# DM2097_HUB.net
KiCad netlist of a schematic drawn in Altium Designer
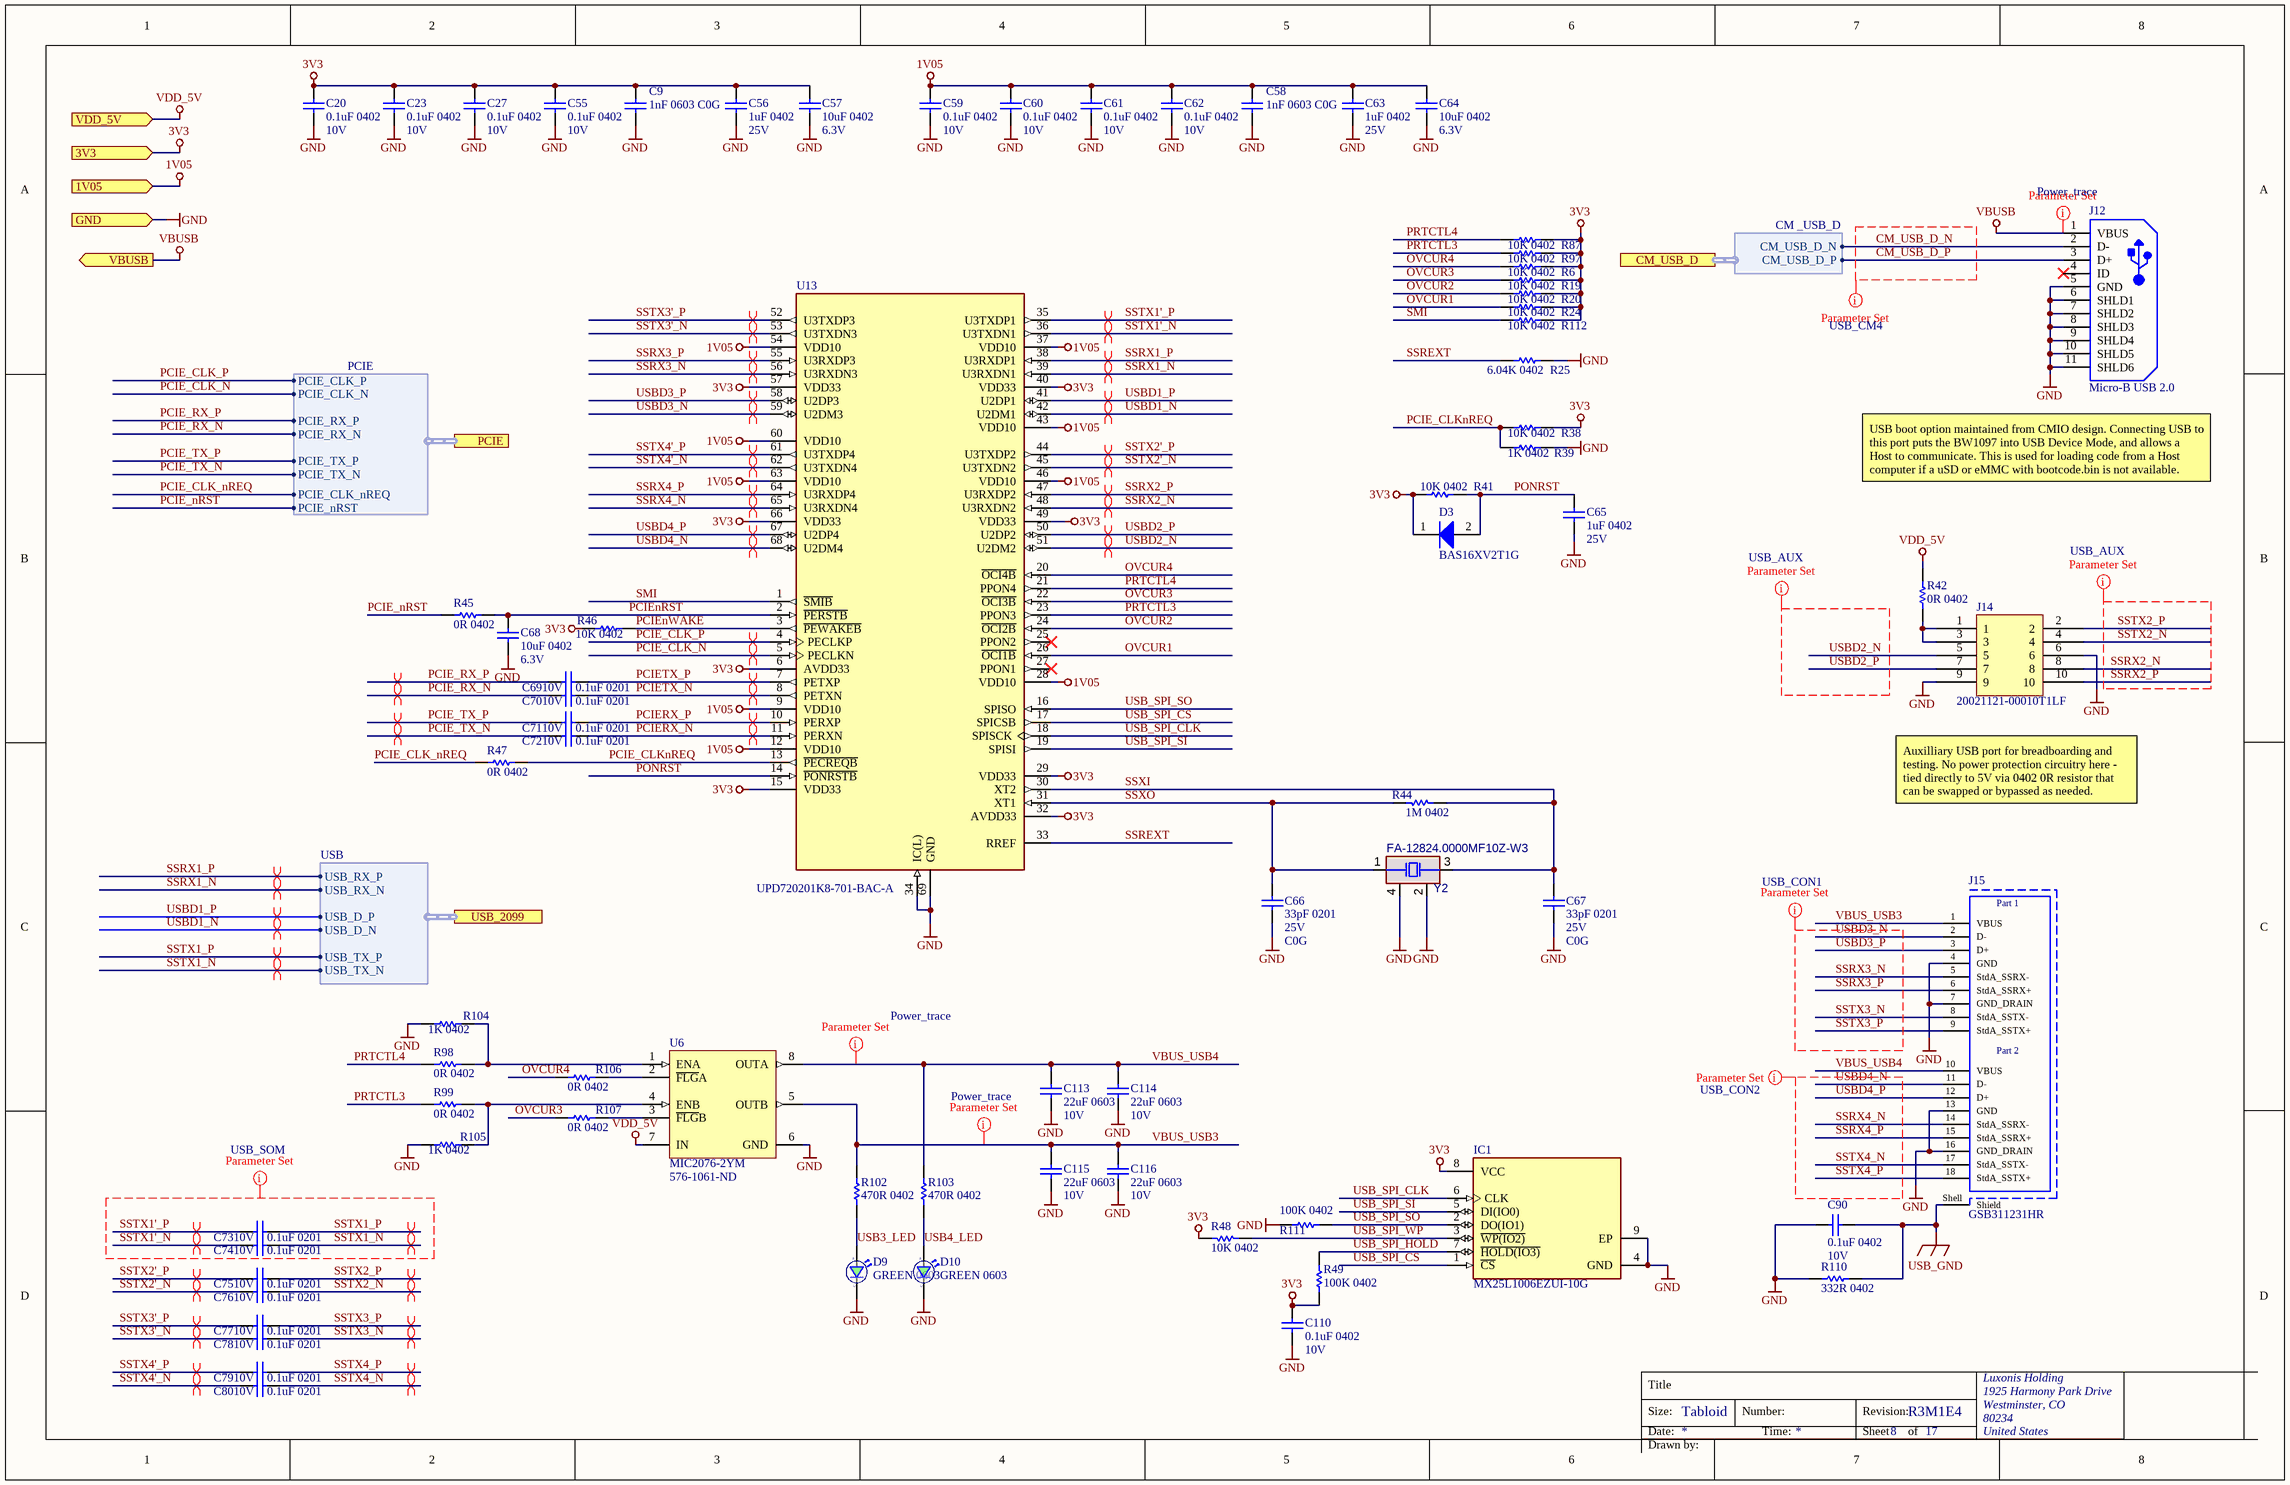
[diagram p0: DM2097_HUB.SchDoc]

(export (version "E")
  (design (tool "Eeschema 10.0.6"))
  (components
    (comp (ref "C9")
      (value "1nF 0603 C0G")
      (footprint "CAP_Altium_Vault_Generic:CAPC0603(1608)100_N")
      (description "CAP CER 1000PF 50V C0G/NP0 0603")
      (fields
        (field (name "MANUFACTURER") "Murata")
        (field (name "MANUFACTURER PART NUMBER") "GRM1885C1H102FA01D")
      )
      (libsource (lib "LuxonisMaster") (part "GRM1885C1H102FA01D"))
    )
    (comp (ref "C20")
      (value "0.1uF 0402")
      (footprint "CAP_Altium_Vault_Generic:CAPC0402(1005)70_N")
      (description "CAP CER 0.1UF 10V X7R 0402 5%")
      (fields (field (name "TOLERANCE") "5%") (field (name "VOLTAGE RATING") "10V"))
      (libsource (lib "LuxonisMaster") (part "GRM155R71A104JA01D"))
    )
    (comp (ref "C23")
      (value "0.1uF 0402")
      (footprint "CAP_Altium_Vault_Generic:CAPC0402(1005)70_N")
      (description "CAP CER 0.1UF 10V X7R 0402 5%")
      (fields (field (name "TOLERANCE") "5%") (field (name "VOLTAGE RATING") "10V"))
      (libsource (lib "LuxonisMaster") (part "GRM155R71A104JA01D"))
    )
    (comp (ref "C27")
      (value "0.1uF 0402")
      (footprint "CAP_Altium_Vault_Generic:CAPC0402(1005)70_N")
      (description "CAP CER 0.1UF 10V X7R 0402 5%")
      (fields (field (name "TOLERANCE") "5%") (field (name "VOLTAGE RATING") "10V"))
      (libsource (lib "LuxonisMaster") (part "GRM155R71A104JA01D"))
    )
    (comp (ref "C55")
      (value "0.1uF 0402")
      (footprint "CAP_Altium_Vault_Generic:CAPC0402(1005)70_N")
      (description "CAP CER 0.1UF 10V X7R 0402 5%")
      (fields (field (name "TOLERANCE") "5%") (field (name "VOLTAGE RATING") "10V"))
      (libsource (lib "LuxonisMaster") (part "GRM155R71A104JA01D"))
    )
    (comp (ref "C56")
      (value "1uF 0402")
      (footprint "CAP_Altium_Vault_Generic:CAPC0402(1005)70_N")
      (description "CAP CER 1UF 25V X5R 0402 10%")
      (fields
        (field (name "TOLERANCE") "10%")
        (field (name "VOLTAGE") "25V")
        (field (name "VOLTAGE RATING") "25V")
      )
      (libsource (lib "LuxonisMaster") (part "GRM155R61E105KA12D"))
    )
    (comp (ref "C57")
      (value "10uF 0402")
      (footprint "CAP_Altium_Vault_Generic:CAPC0402(1005)70_N")
      (description "CAP CER 10UF 6.3V X5R 0402 20%")
      (fields (field (name "TOLERANCE") "20%") (field (name "VOLTAGE RATING") "6.3V"))
      (libsource (lib "LuxonisMaster") (part "GRM155R60J106ME15D"))
    )
    (comp (ref "C58")
      (value "1nF 0603 C0G")
      (footprint "CAP_Altium_Vault_Generic:CAPC0603(1608)100_N")
      (description "CAP CER 1000PF 50V C0G/NP0 0603")
      (fields
        (field (name "MANUFACTURER") "Murata")
        (field (name "MANUFACTURER PART NUMBER") "GRM1885C1H102FA01D")
      )
      (libsource (lib "LuxonisMaster") (part "GRM1885C1H102FA01D"))
    )
    (comp (ref "C59")
      (value "0.1uF 0402")
      (footprint "CAP_Altium_Vault_Generic:CAPC0402(1005)70_N")
      (description "CAP CER 0.1UF 10V X7R 0402 5%")
      (fields (field (name "TOLERANCE") "5%") (field (name "VOLTAGE RATING") "10V"))
      (libsource (lib "LuxonisMaster") (part "GRM155R71A104JA01D"))
    )
    (comp (ref "C60")
      (value "0.1uF 0402")
      (footprint "CAP_Altium_Vault_Generic:CAPC0402(1005)70_N")
      (description "CAP CER 0.1UF 10V X7R 0402 5%")
      (fields (field (name "TOLERANCE") "5%") (field (name "VOLTAGE RATING") "10V"))
      (libsource (lib "LuxonisMaster") (part "GRM155R71A104JA01D"))
    )
    (comp (ref "C61")
      (value "0.1uF 0402")
      (footprint "CAP_Altium_Vault_Generic:CAPC0402(1005)70_N")
      (description "CAP CER 0.1UF 10V X7R 0402 5%")
      (fields (field (name "TOLERANCE") "5%") (field (name "VOLTAGE RATING") "10V"))
      (libsource (lib "LuxonisMaster") (part "GRM155R71A104JA01D"))
    )
    (comp (ref "C62")
      (value "0.1uF 0402")
      (footprint "CAP_Altium_Vault_Generic:CAPC0402(1005)70_N")
      (description "CAP CER 0.1UF 10V X7R 0402 5%")
      (fields (field (name "TOLERANCE") "5%") (field (name "VOLTAGE RATING") "10V"))
      (libsource (lib "LuxonisMaster") (part "GRM155R71A104JA01D"))
    )
    (comp (ref "C63")
      (value "1uF 0402")
      (footprint "CAP_Altium_Vault_Generic:CAPC0402(1005)70_N")
      (description "CAP CER 1UF 25V X5R 0402 10%")
      (fields
        (field (name "TOLERANCE") "10%")
        (field (name "VOLTAGE") "25V")
        (field (name "VOLTAGE RATING") "25V")
      )
      (libsource (lib "LuxonisMaster") (part "GRM155R61E105KA12D"))
    )
    (comp (ref "C64")
      (value "10uF 0402")
      (footprint "CAP_Altium_Vault_Generic:CAPC0402(1005)70_N")
      (description "CAP CER 10UF 6.3V X5R 0402 20%")
      (fields (field (name "TOLERANCE") "20%") (field (name "VOLTAGE RATING") "6.3V"))
      (libsource (lib "LuxonisMaster") (part "GRM155R60J106ME15D"))
    )
    (comp (ref "C65")
      (value "1uF 0402")
      (footprint "CAP_Altium_Vault_Generic:CAPC0402(1005)70_N")
      (description "CAP CER 1UF 25V X5R 0402 10%")
      (fields
        (field (name "TOLERANCE") "10%")
        (field (name "VOLTAGE") "25V")
        (field (name "VOLTAGE RATING") "25V")
      )
      (libsource (lib "LuxonisMaster") (part "GRM155R61E105KA12D"))
    )
    (comp (ref "C66")
      (value "33pF 0201")
      (footprint "CAP_Altium_Vault_Generic:CAPC0201(0603)33_L")
      (description "CAP CER 33PF 25V C0G/NP0 0201")
      (fields
        (field (name "TOLERANCE") "5%")
        (field (name "VOLTAGE RATING") "25V")
        (field (name "DIELECTRIC") "C0G")
      )
      (libsource (lib "LuxonisMaster") (part "GRM0335C1E330JA01D"))
    )
    (comp (ref "C67")
      (value "33pF 0201")
      (footprint "CAP_Altium_Vault_Generic:CAPC0201(0603)33_L")
      (description "CAP CER 33PF 25V C0G/NP0 0201")
      (fields
        (field (name "TOLERANCE") "5%")
        (field (name "VOLTAGE RATING") "25V")
        (field (name "DIELECTRIC") "C0G")
      )
      (libsource (lib "LuxonisMaster") (part "GRM0335C1E330JA01D"))
    )
    (comp (ref "C68")
      (value "10uF 0402")
      (footprint "CAP_Altium_Vault_Generic:CAPC0402(1005)70_N")
      (description "CAP CER 10UF 6.3V X5R 0402 20%")
      (fields (field (name "TOLERANCE") "20%") (field (name "VOLTAGE RATING") "6.3V"))
      (libsource (lib "LuxonisMaster") (part "GRM155R60J106ME15D"))
    )
    (comp (ref "C69")
      (value "0.1uF 0201")
      (footprint "CAP_Altium_Vault_Generic:CAPC0201(0603)33_L")
      (description "CAP CER 0.1UF 10V X5R 0201")
      (fields (field (name "TOLERANCE") "10%") (field (name "VOLTAGE") "10V"))
      (libsource (lib "LuxonisMaster") (part "GRM033R61A104KE15D"))
    )
    (comp (ref "C70")
      (value "0.1uF 0201")
      (footprint "CAP_Altium_Vault_Generic:CAPC0201(0603)33_L")
      (description "CAP CER 0.1UF 10V X5R 0201")
      (fields (field (name "TOLERANCE") "10%") (field (name "VOLTAGE") "10V"))
      (libsource (lib "LuxonisMaster") (part "GRM033R61A104KE15D"))
    )
    (comp (ref "C71")
      (value "0.1uF 0201")
      (footprint "CAP_Altium_Vault_Generic:CAPC0201(0603)33_L")
      (description "CAP CER 0.1UF 10V X5R 0201")
      (fields (field (name "TOLERANCE") "10%") (field (name "VOLTAGE") "10V"))
      (libsource (lib "LuxonisMaster") (part "GRM033R61A104KE15D"))
    )
    (comp (ref "C72")
      (value "0.1uF 0201")
      (footprint "CAP_Altium_Vault_Generic:CAPC0201(0603)33_L")
      (description "CAP CER 0.1UF 10V X5R 0201")
      (fields (field (name "TOLERANCE") "10%") (field (name "VOLTAGE") "10V"))
      (libsource (lib "LuxonisMaster") (part "GRM033R61A104KE15D"))
    )
    (comp (ref "C73")
      (value "0.1uF 0201")
      (footprint "CAP_Altium_Vault_Generic:CAPC0201(0603)33_L")
      (description "CAP CER 0.1UF 10V X5R 0201")
      (fields (field (name "TOLERANCE") "10%") (field (name "VOLTAGE") "10V"))
      (libsource (lib "LuxonisMaster") (part "GRM033R61A104KE15D"))
    )
    (comp (ref "C74")
      (value "0.1uF 0201")
      (footprint "CAP_Altium_Vault_Generic:CAPC0201(0603)33_L")
      (description "CAP CER 0.1UF 10V X5R 0201")
      (fields (field (name "TOLERANCE") "10%") (field (name "VOLTAGE") "10V"))
      (libsource (lib "LuxonisMaster") (part "GRM033R61A104KE15D"))
    )
    (comp (ref "C75")
      (value "0.1uF 0201")
      (footprint "CAP_Altium_Vault_Generic:CAPC0201(0603)33_L")
      (description "CAP CER 0.1UF 10V X5R 0201")
      (fields (field (name "TOLERANCE") "10%") (field (name "VOLTAGE") "10V"))
      (libsource (lib "LuxonisMaster") (part "GRM033R61A104KE15D"))
    )
    (comp (ref "C76")
      (value "0.1uF 0201")
      (footprint "CAP_Altium_Vault_Generic:CAPC0201(0603)33_L")
      (description "CAP CER 0.1UF 10V X5R 0201")
      (fields (field (name "TOLERANCE") "10%") (field (name "VOLTAGE") "10V"))
      (libsource (lib "LuxonisMaster") (part "GRM033R61A104KE15D"))
    )
    (comp (ref "C77")
      (value "0.1uF 0201")
      (footprint "CAP_Altium_Vault_Generic:CAPC0201(0603)33_L")
      (description "CAP CER 0.1UF 10V X5R 0201")
      (fields (field (name "TOLERANCE") "10%") (field (name "VOLTAGE") "10V"))
      (libsource (lib "LuxonisMaster") (part "GRM033R61A104KE15D"))
    )
    (comp (ref "C78")
      (value "0.1uF 0201")
      (footprint "CAP_Altium_Vault_Generic:CAPC0201(0603)33_L")
      (description "CAP CER 0.1UF 10V X5R 0201")
      (fields (field (name "TOLERANCE") "10%") (field (name "VOLTAGE") "10V"))
      (libsource (lib "LuxonisMaster") (part "GRM033R61A104KE15D"))
    )
    (comp (ref "C79")
      (value "0.1uF 0201")
      (footprint "CAP_Altium_Vault_Generic:CAPC0201(0603)33_L")
      (description "CAP CER 0.1UF 10V X5R 0201")
      (fields (field (name "TOLERANCE") "10%") (field (name "VOLTAGE") "10V"))
      (libsource (lib "LuxonisMaster") (part "GRM033R61A104KE15D"))
    )
    (comp (ref "C80")
      (value "0.1uF 0201")
      (footprint "CAP_Altium_Vault_Generic:CAPC0201(0603)33_L")
      (description "CAP CER 0.1UF 10V X5R 0201")
      (fields (field (name "TOLERANCE") "10%") (field (name "VOLTAGE") "10V"))
      (libsource (lib "LuxonisMaster") (part "GRM033R61A104KE15D"))
    )
    (comp (ref "C90")
      (value "0.1uF 0402")
      (footprint "CAP_Altium_Vault_Generic:CAPC0402(1005)70_N")
      (description "CAP CER 0.1UF 10V X7R 0402 5%")
      (fields (field (name "TOLERANCE") "5%") (field (name "VOLTAGE RATING") "10V"))
      (libsource (lib "LuxonisMaster") (part "GRM155R71A104JA01D"))
    )
    (comp (ref "C110")
      (value "0.1uF 0402")
      (footprint "CAP_Altium_Vault_Generic:CAPC0402(1005)70_N")
      (description "CAP CER 0.1UF 10V X7R 0402 5%")
      (fields (field (name "TOLERANCE") "5%") (field (name "VOLTAGE RATING") "10V"))
      (libsource (lib "LuxonisMaster") (part "GRM155R71A104JA01D"))
    )
    (comp (ref "C113")
      (value "22uF 0603")
      (footprint "CAP_Altium_Vault_Generic:CAPC0603(1608)100_N")
      (description "CAP CER 22UF 10V X5R 0603 20%")
      (fields (field (name "TOLERANCE") "20%") (field (name "VOLTAGE RATING") "10V"))
      (libsource (lib "LuxonisMaster") (part "GRM188R61A226ME15D"))
    )
    (comp (ref "C114")
      (value "22uF 0603")
      (footprint "CAP_Altium_Vault_Generic:CAPC0603(1608)100_N")
      (description "CAP CER 22UF 10V X5R 0603 20%")
      (fields (field (name "TOLERANCE") "20%") (field (name "VOLTAGE RATING") "10V"))
      (libsource (lib "LuxonisMaster") (part "GRM188R61A226ME15D"))
    )
    (comp (ref "C115")
      (value "22uF 0603")
      (footprint "CAP_Altium_Vault_Generic:CAPC0603(1608)100_N")
      (description "CAP CER 22UF 10V X5R 0603 20%")
      (fields (field (name "TOLERANCE") "20%") (field (name "VOLTAGE RATING") "10V"))
      (libsource (lib "LuxonisMaster") (part "GRM188R61A226ME15D"))
    )
    (comp (ref "C116")
      (value "22uF 0603")
      (footprint "CAP_Altium_Vault_Generic:CAPC0603(1608)100_N")
      (description "CAP CER 22UF 10V X5R 0603 20%")
      (fields (field (name "TOLERANCE") "20%") (field (name "VOLTAGE RATING") "10V"))
      (libsource (lib "LuxonisMaster") (part "GRM188R61A226ME15D"))
    )
    (comp (ref "D3")
      (value "BAS16XV2T1G")
      (footprint "BAS16XV2T1G")
      (description "DIODE GEN PURP 75V 200MA SOD523")
      (libsource (lib "Luxonis") (part "Symbol"))
    )
    (comp (ref "D9")
      (value "GREEN 0603")
      (footprint "LuxonisMaster:SML_D1xx8W")
      (description "LED GREEN DIFFUSED 0603 SMD Green 572nm LED Indication - Discrete 2.2V 0603 (1608 Metric)")
      (fields (field (name "MANUFACTURER") "Rohm") (field (name "MANUFACTURER PART NUMBER") "SML-D12M8WT86"))
      (libsource (lib "LuxonisMaster") (part "SML-D12M8WT86"))
    )
    (comp (ref "D10")
      (value "GREEN 0603")
      (footprint "LuxonisMaster:SML_D1xx8W")
      (description "LED GREEN DIFFUSED 0603 SMD Green 572nm LED Indication - Discrete 2.2V 0603 (1608 Metric)")
      (fields (field (name "MANUFACTURER") "Rohm") (field (name "MANUFACTURER PART NUMBER") "SML-D12M8WT86"))
      (libsource (lib "LuxonisMaster") (part "SML-D12M8WT86"))
    )
    (comp (ref "IC1")
      (value "MX25L1006EZUI-10G")
      (footprint "MX25L1006EZUI-10G-Footprint-1")
      (description "Flash, 512KX2, PDSO8")
      (libsource (lib "Luxonis LLC") (part "MX25L1006EZUI-10G-Symbol-1"))
    )
    (comp (ref "J12")
      (value "Micro-B USB 2.0")
      (footprint "LuxonisMaster:10118194-0001LF")
      (libsource (lib "LuxonisMaster") (part "10118194-0001LF"))
    )
    (comp (ref "J14")
      (value "20021121-00010T1LF")
      (footprint "LuxonisMaster:20021121-00010T1LF")
      (description "CONN HEADER SMD 10POS 1.27MM")
      (libsource (lib "LuxonisMaster") (part "20021121-00010T1LF"))
    )
    (comp (ref "J15")
      (value "GSB311231HR")
      (footprint "GSB311231HR")
      (description "USB Connector, 18 Contact(s), Female, Right Angle, Solder Terminal")
      (fields (field (name "MANUFACTURER") "Amphenol Commercial"))
      (libsource (lib "DM1097_R1M1E1") (part "GSB311231HR"))
    )
    (comp (ref "R6")
      (value "10K 0402")
      (footprint "RES_Altium_Vault_Generic:RESC0402(1005)_N")
      (fields (field (name "TOLERANCE") "1%"))
      (libsource (lib "LuxonisMaster") (part "RC0402FR-1310KL"))
    )
    (comp (ref "R19")
      (value "10K 0402")
      (footprint "RES_Altium_Vault_Generic:RESC0402(1005)_N")
      (fields (field (name "TOLERANCE") "1%"))
      (libsource (lib "LuxonisMaster") (part "RC0402FR-1310KL"))
    )
    (comp (ref "R20")
      (value "10K 0402")
      (footprint "RES_Altium_Vault_Generic:RESC0402(1005)_N")
      (fields (field (name "TOLERANCE") "1%"))
      (libsource (lib "LuxonisMaster") (part "RC0402FR-1310KL"))
    )
    (comp (ref "R24")
      (value "10K 0402")
      (footprint "RES_Altium_Vault_Generic:RESC0402(1005)_N")
      (fields (field (name "TOLERANCE") "1%"))
      (libsource (lib "LuxonisMaster") (part "RC0402FR-1310KL"))
    )
    (comp (ref "R25")
      (value "6.04K 0402")
      (footprint "RESC0402(1005)_L")
      (fields (field (name "TOLERANCE") "1%"))
      (libsource (lib "") (part "Symbol_1"))
    )
    (comp (ref "R38")
      (value "10K 0402")
      (footprint "RES_Altium_Vault_Generic:RESC0402(1005)_N")
      (fields (field (name "TOLERANCE") "1%"))
      (libsource (lib "LuxonisMaster") (part "RC0402FR-1310KL"))
    )
    (comp (ref "R39")
      (value "1K 0402")
      (footprint "RESC0402(1005)_L")
      (fields (field (name "TOLERANCE") "1%"))
      (libsource (lib "LuxonisMaster") (part "Symbol"))
    )
    (comp (ref "R41")
      (value "10K 0402")
      (footprint "RES_Altium_Vault_Generic:RESC0402(1005)_N")
      (fields (field (name "TOLERANCE") "1%"))
      (libsource (lib "LuxonisMaster") (part "RC0402FR-1310KL"))
    )
    (comp (ref "R42")
      (value "0R 0402")
      (footprint "RES_Altium_Vault_Generic:RESC0402(1005)_N")
      (description "RES SMD 0 OHM JUMPER 1/16W 0402")
      (fields (field (name "TOLERANCE") "5%"))
      (libsource (lib "LuxonisMaster") (part "CRCW04020000Z0ED"))
    )
    (comp (ref "R44")
      (value "1M 0402")
      (footprint "RES_Altium_Vault_Generic:RESC0402(1005)_N")
      (description "RES SMD 1M OHM 1% 1/16W 0402")
      (fields (field (name "TOLERANCE") "1%"))
      (libsource (lib "LuxonisMaster") (part "RC0402FR-071ML"))
    )
    (comp (ref "R45")
      (value "0R 0402")
      (footprint "RES_Altium_Vault_Generic:RESC0402(1005)_N")
      (description "RES SMD 0 OHM JUMPER 1/16W 0402")
      (fields (field (name "TOLERANCE") "5%"))
      (libsource (lib "LuxonisMaster") (part "CRCW04020000Z0ED"))
    )
    (comp (ref "R46")
      (value "10K 0402")
      (footprint "RES_Altium_Vault_Generic:RESC0402(1005)_N")
      (fields (field (name "TOLERANCE") "1%"))
      (libsource (lib "LuxonisMaster") (part "RC0402FR-1310KL"))
    )
    (comp (ref "R47")
      (value "0R 0402")
      (footprint "RES_Altium_Vault_Generic:RESC0402(1005)_N")
      (description "RES SMD 0 OHM JUMPER 1/16W 0402")
      (fields (field (name "TOLERANCE") "5%"))
      (libsource (lib "LuxonisMaster") (part "CRCW04020000Z0ED"))
    )
    (comp (ref "R48")
      (value "10K 0402")
      (footprint "RES_Altium_Vault_Generic:RESC0402(1005)_N")
      (fields (field (name "TOLERANCE") "1%"))
      (libsource (lib "LuxonisMaster") (part "RC0402FR-1310KL"))
    )
    (comp (ref "R49")
      (value "100K 0402")
      (footprint "RES_Altium_Vault_Generic:RESC0402(1005)_L")
      (description "RES SMD 100K OHM 1% 1/16W 0402")
      (fields (field (name "TOLERANCE") "1%"))
      (libsource (lib "LuxonisMaster") (part "RC0402FR-07100KL"))
    )
    (comp (ref "R87")
      (value "10K 0402")
      (footprint "RES_Altium_Vault_Generic:RESC0402(1005)_N")
      (fields (field (name "TOLERANCE") "1%"))
      (libsource (lib "LuxonisMaster") (part "RC0402FR-1310KL"))
    )
    (comp (ref "R97")
      (value "10K 0402")
      (footprint "RES_Altium_Vault_Generic:RESC0402(1005)_N")
      (fields (field (name "TOLERANCE") "1%"))
      (libsource (lib "LuxonisMaster") (part "RC0402FR-1310KL"))
    )
    (comp (ref "R98")
      (value "0R 0402")
      (footprint "RES_Altium_Vault_Generic:RESC0402(1005)_N")
      (description "RES SMD 0 OHM JUMPER 1/16W 0402")
      (fields (field (name "TOLERANCE") "5%"))
      (libsource (lib "LuxonisMaster") (part "CRCW04020000Z0ED"))
    )
    (comp (ref "R99")
      (value "0R 0402")
      (footprint "RES_Altium_Vault_Generic:RESC0402(1005)_N")
      (description "RES SMD 0 OHM JUMPER 1/16W 0402")
      (fields (field (name "TOLERANCE") "5%"))
      (libsource (lib "LuxonisMaster") (part "CRCW04020000Z0ED"))
    )
    (comp (ref "R102")
      (value "470R 0402")
      (footprint "RES_Altium_Vault_Generic:RESC0402(1005)_N")
      (description "RES SMD 470 OHM 1% 1/16W 0402")
      (fields (field (name "TOLERANCE") "1%"))
      (libsource (lib "LuxonisMaster") (part "CRCW0402470RFKED"))
    )
    (comp (ref "R103")
      (value "470R 0402")
      (footprint "RES_Altium_Vault_Generic:RESC0402(1005)_N")
      (description "RES SMD 470 OHM 1% 1/16W 0402")
      (fields (field (name "TOLERANCE") "1%"))
      (libsource (lib "LuxonisMaster") (part "CRCW0402470RFKED"))
    )
    (comp (ref "R104")
      (value "1K 0402")
      (footprint "RESC0402(1005)_L")
      (fields (field (name "TOLERANCE") "1%"))
      (libsource (lib "LuxonisMaster") (part "Symbol"))
    )
    (comp (ref "R105")
      (value "1K 0402")
      (footprint "RESC0402(1005)_L")
      (fields (field (name "TOLERANCE") "1%"))
      (libsource (lib "LuxonisMaster") (part "Symbol"))
    )
    (comp (ref "R106")
      (value "0R 0402")
      (footprint "RES_Altium_Vault_Generic:RESC0402(1005)_N")
      (description "RES SMD 0 OHM JUMPER 1/16W 0402")
      (fields (field (name "TOLERANCE") "5%"))
      (libsource (lib "LuxonisMaster") (part "CRCW04020000Z0ED"))
    )
    (comp (ref "R107")
      (value "0R 0402")
      (footprint "RES_Altium_Vault_Generic:RESC0402(1005)_N")
      (description "RES SMD 0 OHM JUMPER 1/16W 0402")
      (fields (field (name "TOLERANCE") "5%"))
      (libsource (lib "LuxonisMaster") (part "CRCW04020000Z0ED"))
    )
    (comp (ref "R110")
      (value "332R 0402")
      (footprint "RES_Altium_Vault_Generic:RESC0402(1005)_N")
      (description "RES SMD 332 OHM 1% 1/16W 0402")
      (fields (field (name "TOLERANCE") "1%"))
      (libsource (lib "LuxonisMaster") (part "RC0402FR-07332RL"))
    )
    (comp (ref "R111")
      (value "100K 0402")
      (footprint "RES_Altium_Vault_Generic:RESC0402(1005)_L")
      (description "RES SMD 100K OHM 1% 1/16W 0402")
      (fields (field (name "TOLERANCE") "1%"))
      (libsource (lib "LuxonisMaster") (part "RC0402FR-07100KL"))
    )
    (comp (ref "R112")
      (value "10K 0402")
      (footprint "RES_Altium_Vault_Generic:RESC0402(1005)_N")
      (fields (field (name "TOLERANCE") "1%"))
      (libsource (lib "LuxonisMaster") (part "RC0402FR-1310KL"))
    )
    (comp (ref "U6")
      (value "MIC2076-2YM")
      (footprint "MIC2076-2YM")
      (description "Power Supply Support Circuit, Fixed, 2 Channel, 2.4, PDSO8")
      (fields (field (name "SUPPLIER PART NUMBER 1") "576-1061-ND"))
      (libsource (lib "DM1097_R1M1E1") (part "MIC2076-2YM"))
    )
    (comp (ref "U13")
      (value "UPD720201K8-701-BAC-A")
      (footprint "QFN40P800X800X90-69N")
      (description "USB Host Controller USB 3.0 USB Interface 68-QFN (8x8)")
      (fields (field (name "DIGI-KEY_PART_NUMBER") "UPD720201K8-701-BAC-A-ND"))
      (libsource (lib "Luxonis LLC") (part "UPD720201K8-701-BAC-A"))
    )
    (comp (ref "Y2")
      (value "FA-12824.0000MF10Z-W3")
      (footprint "EPSON-FA-128_V")
      (description "Crystal, 24 MHz, +/- 10 ppm, -20 to 75 degC, 4-Pin SMD, RoHS, Tape and Reel")
      (libsource (lib "Luxonis LLC") (part "CMP-00014-7"))
    )
  )
  (nets
    (net (code "5") (name "/CM_USB_D_N") (class "Default")
      (node (ref "J12") (pin "2") (pinfunction "D-_2") (pintype "passive"))
    )
    (net (code "6") (name "/CM_USB_D_P") (class "Default")
      (node (ref "J12") (pin "3") (pinfunction "D+_3") (pintype "passive"))
    )
    (net (code "7") (name "/OVCUR1") (class "Default")
      (node (ref "R24") (pin "1") (pinfunction "1_1") (pintype "passive"))
      (node (ref "U13") (pin "26") (pinfunction "~{OCI1B}_26") (pintype "input"))
    )
    (net (code "8") (name "/OVCUR2") (class "Default")
      (node (ref "R20") (pin "1") (pinfunction "1_1") (pintype "passive"))
      (node (ref "U13") (pin "24") (pinfunction "~{OCI2B}_24") (pintype "input"))
    )
    (net (code "9") (name "/OVCUR3") (class "Default")
      (node (ref "R107") (pin "2") (pinfunction "2_2") (pintype "passive"))
      (node (ref "R19") (pin "1") (pinfunction "1_1") (pintype "passive"))
      (node (ref "U13") (pin "22") (pinfunction "~{OCI3B}_22") (pintype "input"))
    )
    (net (code "10") (name "/OVCUR4") (class "Default")
      (node (ref "R106") (pin "2") (pinfunction "2_2") (pintype "passive"))
      (node (ref "R6") (pin "1") (pinfunction "1_1") (pintype "passive"))
      (node (ref "U13") (pin "20") (pinfunction "~{OCI4B}_20") (pintype "input"))
    )
    (net (code "11") (name "/PCIERX_N") (class "Default")
      (node (ref "C72") (pin "2") (pinfunction "2_2") (pintype "passive"))
      (node (ref "U13") (pin "11") (pinfunction "PERXN_11") (pintype "input"))
    )
    (net (code "12") (name "/PCIERX_P") (class "Default")
      (node (ref "C71") (pin "2") (pinfunction "2_2") (pintype "passive"))
      (node (ref "U13") (pin "10") (pinfunction "PERXP_10") (pintype "input"))
    )
    (net (code "13") (name "/PCIETX_N") (class "Default")
      (node (ref "C70") (pin "2") (pinfunction "2_2") (pintype "passive"))
      (node (ref "U13") (pin "8") (pinfunction "PETXN_8") (pintype "output"))
    )
    (net (code "14") (name "/PCIETX_P") (class "Default")
      (node (ref "C69") (pin "2") (pinfunction "2_2") (pintype "passive"))
      (node (ref "U13") (pin "7") (pinfunction "PETXP_7") (pintype "output"))
    )
    (net (code "15") (name "/PCIE_CLK_N") (class "Default")
      (node (ref "U13") (pin "5") (pinfunction "PECLKN_5") (pintype "input"))
    )
    (net (code "16") (name "/PCIE_CLK_P") (class "Default")
      (node (ref "U13") (pin "4") (pinfunction "PECLKP_4") (pintype "input"))
    )
    (net (code "17") (name "/PCIE_CLK_nREQ") (class "Default")
      (node (ref "R47") (pin "1") (pinfunction "1_1") (pintype "passive"))
    )
    (net (code "18") (name "/PCIE_CLKnREQ") (class "Default")
      (node (ref "R38") (pin "1") (pinfunction "1_1") (pintype "passive"))
      (node (ref "R39") (pin "1") (pinfunction "1_1") (pintype "passive"))
      (node (ref "R47") (pin "2") (pinfunction "2_2") (pintype "passive"))
      (node (ref "U13") (pin "13") (pinfunction "~{PECREQB}_13") (pintype "output"))
    )
    (net (code "19") (name "/PCIE_RX_N") (class "Default")
      (node (ref "C70") (pin "1") (pinfunction "1_1") (pintype "passive"))
    )
    (net (code "20") (name "/PCIE_RX_P") (class "Default")
      (node (ref "C69") (pin "1") (pinfunction "1_1") (pintype "passive"))
    )
    (net (code "21") (name "/PCIE_TX_N") (class "Default")
      (node (ref "C72") (pin "1") (pinfunction "1_1") (pintype "passive"))
    )
    (net (code "22") (name "/PCIE_TX_P") (class "Default")
      (node (ref "C71") (pin "1") (pinfunction "1_1") (pintype "passive"))
    )
    (net (code "23") (name "/PCIE_nRST") (class "Default")
      (node (ref "R45") (pin "1") (pinfunction "1_1") (pintype "passive"))
    )
    (net (code "24") (name "/PCIEnRST") (class "Default")
      (node (ref "C68") (pin "2") (pinfunction "2_2") (pintype "passive"))
      (node (ref "R45") (pin "2") (pinfunction "2_2") (pintype "passive"))
      (node (ref "U13") (pin "2") (pinfunction "~{PERSTB}_2") (pintype "input"))
    )
    (net (code "25") (name "/PCIEnWAKE") (class "Default")
      (node (ref "R46") (pin "2") (pinfunction "2_2") (pintype "passive"))
      (node (ref "U13") (pin "3") (pinfunction "~{PEWAKEB}_3") (pintype "output"))
    )
    (net (code "26") (name "/PONRST") (class "Default")
      (node (ref "C65") (pin "2") (pinfunction "2_2") (pintype "passive"))
      (node (ref "D3") (pin "2") (pinfunction "A_2") (pintype "passive"))
      (node (ref "R41") (pin "2") (pinfunction "2_2") (pintype "passive"))
      (node (ref "U13") (pin "14") (pinfunction "~{PONRSTB}_14") (pintype "input"))
    )
    (net (code "27") (name "/PRTCTL3") (class "Default")
      (node (ref "R97") (pin "1") (pinfunction "1_1") (pintype "passive"))
      (node (ref "R99") (pin "2") (pinfunction "2_2") (pintype "passive"))
      (node (ref "U13") (pin "23") (pinfunction "PPON3_23") (pintype "output"))
    )
    (net (code "28") (name "/PRTCTL4") (class "Default")
      (node (ref "R87") (pin "1") (pinfunction "1_1") (pintype "passive"))
      (node (ref "R98") (pin "2") (pinfunction "2_2") (pintype "passive"))
      (node (ref "U13") (pin "21") (pinfunction "PPON4_21") (pintype "output"))
    )
    (net (code "29") (name "/SMI") (class "Default")
      (node (ref "R112") (pin "1") (pinfunction "1_1") (pintype "passive"))
      (node (ref "U13") (pin "1") (pinfunction "~{SMIB}_1") (pintype "output"))
    )
    (net (code "30") (name "/SSREXT") (class "Default")
      (node (ref "R25") (pin "1") (pinfunction "1_1") (pintype "passive"))
      (node (ref "U13") (pin "33") (pinfunction "RREF_33") (pintype "passive"))
    )
    (net (code "31") (name "/SSRX1_N") (class "Default")
      (node (ref "U13") (pin "39") (pinfunction "U3RXDN1_39") (pintype "input"))
    )
    (net (code "32") (name "/SSRX1_P") (class "Default")
      (node (ref "U13") (pin "38") (pinfunction "U3RXDP1_38") (pintype "input"))
    )
    (net (code "33") (name "/SSRX2_N") (class "Default")
      (node (ref "J14") (pin "8") (pinfunction "8_8") (pintype "passive"))
      (node (ref "U13") (pin "48") (pinfunction "U3RXDN2_48") (pintype "input"))
    )
    (net (code "34") (name "/SSRX2_P") (class "Default")
      (node (ref "J14") (pin "10") (pinfunction "10_10") (pintype "passive"))
      (node (ref "U13") (pin "47") (pinfunction "U3RXDP2_47") (pintype "input"))
    )
    (net (code "35") (name "/SSRX3_N") (class "Default")
      (node (ref "J15") (pin "5") (pinfunction "StdA_SSRX-_5") (pintype "passive"))
      (node (ref "U13") (pin "56") (pinfunction "U3RXDN3_56") (pintype "input"))
    )
    (net (code "36") (name "/SSRX3_P") (class "Default")
      (node (ref "J15") (pin "6") (pinfunction "StdA_SSRX+_6") (pintype "passive"))
      (node (ref "U13") (pin "55") (pinfunction "U3RXDP3_55") (pintype "input"))
    )
    (net (code "37") (name "/SSRX4_N") (class "Default")
      (node (ref "J15") (pin "14") (pinfunction "StdA_SSRX-_14") (pintype "passive"))
      (node (ref "U13") (pin "65") (pinfunction "U3RXDN4_65") (pintype "input"))
    )
    (net (code "38") (name "/SSRX4_P") (class "Default")
      (node (ref "J15") (pin "15") (pinfunction "StdA_SSRX+_15") (pintype "passive"))
      (node (ref "U13") (pin "64") (pinfunction "U3RXDP4_64") (pintype "input"))
    )
    (net (code "39") (name "/SSTX1'_N") (class "Default")
      (node (ref "C74") (pin "1") (pinfunction "1_1") (pintype "passive"))
      (node (ref "U13") (pin "36") (pinfunction "U3TXDN1_36") (pintype "output"))
    )
    (net (code "40") (name "/SSTX1'_P") (class "Default")
      (node (ref "C73") (pin "1") (pinfunction "1_1") (pintype "passive"))
      (node (ref "U13") (pin "35") (pinfunction "U3TXDP1_35") (pintype "output"))
    )
    (net (code "41") (name "/SSTX1_N") (class "Default")
      (node (ref "C74") (pin "2") (pinfunction "2_2") (pintype "passive"))
    )
    (net (code "42") (name "/SSTX1_P") (class "Default")
      (node (ref "C73") (pin "2") (pinfunction "2_2") (pintype "passive"))
    )
    (net (code "43") (name "/SSTX2'_N") (class "Default")
      (node (ref "C76") (pin "1") (pinfunction "1_1") (pintype "passive"))
      (node (ref "U13") (pin "45") (pinfunction "U3TXDN2_45") (pintype "output"))
    )
    (net (code "44") (name "/SSTX2'_P") (class "Default")
      (node (ref "C75") (pin "1") (pinfunction "1_1") (pintype "passive"))
      (node (ref "U13") (pin "44") (pinfunction "U3TXDP2_44") (pintype "output"))
    )
    (net (code "45") (name "/SSTX2_N") (class "Default")
      (node (ref "C76") (pin "2") (pinfunction "2_2") (pintype "passive"))
      (node (ref "J14") (pin "4") (pinfunction "4_4") (pintype "passive"))
    )
    (net (code "46") (name "/SSTX2_P") (class "Default")
      (node (ref "C75") (pin "2") (pinfunction "2_2") (pintype "passive"))
      (node (ref "J14") (pin "2") (pinfunction "2_2") (pintype "passive"))
    )
    (net (code "47") (name "/SSTX3'_N") (class "Default")
      (node (ref "C78") (pin "1") (pinfunction "1_1") (pintype "passive"))
      (node (ref "U13") (pin "53") (pinfunction "U3TXDN3_53") (pintype "output"))
    )
    (net (code "48") (name "/SSTX3'_P") (class "Default")
      (node (ref "C77") (pin "1") (pinfunction "1_1") (pintype "passive"))
      (node (ref "U13") (pin "52") (pinfunction "U3TXDP3_52") (pintype "output"))
    )
    (net (code "49") (name "/SSTX3_N") (class "Default")
      (node (ref "C78") (pin "2") (pinfunction "2_2") (pintype "passive"))
      (node (ref "J15") (pin "8") (pinfunction "StdA_SSTX-_8") (pintype "passive"))
    )
    (net (code "50") (name "/SSTX3_P") (class "Default")
      (node (ref "C77") (pin "2") (pinfunction "2_2") (pintype "passive"))
      (node (ref "J15") (pin "9") (pinfunction "StdA_SSTX+_9") (pintype "passive"))
    )
    (net (code "51") (name "/SSTX4'_N") (class "Default")
      (node (ref "C80") (pin "1") (pinfunction "1_1") (pintype "passive"))
      (node (ref "U13") (pin "62") (pinfunction "U3TXDN4_62") (pintype "output"))
    )
    (net (code "52") (name "/SSTX4'_P") (class "Default")
      (node (ref "C79") (pin "1") (pinfunction "1_1") (pintype "passive"))
      (node (ref "U13") (pin "61") (pinfunction "U3TXDP4_61") (pintype "output"))
    )
    (net (code "53") (name "/SSTX4_N") (class "Default")
      (node (ref "C80") (pin "2") (pinfunction "2_2") (pintype "passive"))
      (node (ref "J15") (pin "17") (pinfunction "StdA_SSTX-_17") (pintype "passive"))
    )
    (net (code "54") (name "/SSTX4_P") (class "Default")
      (node (ref "C79") (pin "2") (pinfunction "2_2") (pintype "passive"))
      (node (ref "J15") (pin "18") (pinfunction "StdA_SSTX+_18") (pintype "passive"))
    )
    (net (code "55") (name "/SSXI") (class "Default")
      (node (ref "C67") (pin "2") (pinfunction "2_2") (pintype "passive"))
      (node (ref "R44") (pin "1") (pinfunction "1_1") (pintype "passive"))
      (node (ref "U13") (pin "30") (pinfunction "XT2_30") (pintype "output"))
      (node (ref "Y2") (pin "3") (pinfunction "X2_3") (pintype "passive"))
    )
    (net (code "56") (name "/SSXO") (class "Default")
      (node (ref "C66") (pin "2") (pinfunction "2_2") (pintype "passive"))
      (node (ref "R44") (pin "2") (pinfunction "2_2") (pintype "passive"))
      (node (ref "U13") (pin "31") (pinfunction "XT1_31") (pintype "input"))
      (node (ref "Y2") (pin "1") (pinfunction "X1_1") (pintype "passive"))
    )
    (net (code "57") (name "/USB3_LED") (class "Default")
      (node (ref "D9") (pin "2") (pinfunction "A_2") (pintype "passive"))
      (node (ref "R102") (pin "1") (pinfunction "1_1") (pintype "passive"))
    )
    (net (code "58") (name "/USB4_LED") (class "Default")
      (node (ref "D10") (pin "2") (pinfunction "A_2") (pintype "passive"))
      (node (ref "R103") (pin "1") (pinfunction "1_1") (pintype "passive"))
    )
    (net (code "59") (name "/USBD1_N") (class "Default")
      (node (ref "U13") (pin "42") (pinfunction "U2DM1_42") (pintype "bidirectional"))
    )
    (net (code "60") (name "/USBD1_P") (class "Default")
      (node (ref "U13") (pin "41") (pinfunction "U2DP1_41") (pintype "bidirectional"))
    )
    (net (code "61") (name "/USBD2_N") (class "Default")
      (node (ref "J14") (pin "5") (pinfunction "5_5") (pintype "passive"))
      (node (ref "U13") (pin "51") (pinfunction "U2DM2_51") (pintype "bidirectional"))
    )
    (net (code "62") (name "/USBD2_P") (class "Default")
      (node (ref "J14") (pin "7") (pinfunction "7_7") (pintype "passive"))
      (node (ref "U13") (pin "50") (pinfunction "U2DP2_50") (pintype "bidirectional"))
    )
    (net (code "63") (name "/USBD3_N") (class "Default")
      (node (ref "J15") (pin "2") (pinfunction "D-_2") (pintype "passive"))
      (node (ref "U13") (pin "59") (pinfunction "U2DM3_59") (pintype "bidirectional"))
    )
    (net (code "64") (name "/USBD3_P") (class "Default")
      (node (ref "J15") (pin "3") (pinfunction "D+_3") (pintype "passive"))
      (node (ref "U13") (pin "58") (pinfunction "U2DP3_58") (pintype "bidirectional"))
    )
    (net (code "65") (name "/USBD4_N") (class "Default")
      (node (ref "J15") (pin "11") (pinfunction "D-_11") (pintype "passive"))
      (node (ref "U13") (pin "68") (pinfunction "U2DM4_68") (pintype "bidirectional"))
    )
    (net (code "66") (name "/USBD4_P") (class "Default")
      (node (ref "J15") (pin "12") (pinfunction "D+_12") (pintype "passive"))
      (node (ref "U13") (pin "67") (pinfunction "U2DP4_67") (pintype "bidirectional"))
    )
    (net (code "67") (name "/USB_SPI_CLK") (class "Default")
      (node (ref "IC1") (pin "6") (pinfunction "CLK_6") (pintype "input"))
      (node (ref "U13") (pin "18") (pinfunction "SPISCK_18") (pintype "output"))
    )
    (net (code "68") (name "/USB_SPI_CS") (class "Default")
      (node (ref "IC1") (pin "1") (pinfunction "~{CS}_1") (pintype "input"))
      (node (ref "U13") (pin "17") (pinfunction "SPICSB_17") (pintype "output"))
    )
    (net (code "69") (name "/USB_SPI_HOLD") (class "Default")
      (node (ref "IC1") (pin "7") (pinfunction "~{HOLD(IO3)}_7") (pintype "bidirectional"))
      (node (ref "R49") (pin "1") (pinfunction "1_1") (pintype "passive"))
    )
    (net (code "70") (name "/USB_SPI_SI") (class "Default")
      (node (ref "IC1") (pin "5") (pinfunction "DI(IO0)_5") (pintype "bidirectional"))
      (node (ref "U13") (pin "19") (pinfunction "SPISI_19") (pintype "output"))
    )
    (net (code "71") (name "/USB_SPI_SO") (class "Default")
      (node (ref "IC1") (pin "2") (pinfunction "DO(IO1)_2") (pintype "bidirectional"))
      (node (ref "R111") (pin "2") (pinfunction "2_2") (pintype "passive"))
      (node (ref "U13") (pin "16") (pinfunction "SPISO_16") (pintype "input"))
    )
    (net (code "72") (name "/USB_SPI_WP") (class "Default")
      (node (ref "IC1") (pin "3") (pinfunction "~{WP(IO2)}_3") (pintype "bidirectional"))
      (node (ref "R48") (pin "1") (pinfunction "1_1") (pintype "passive"))
    )
    (net (code "73") (name "/VBUS_USB3") (class "Default")
      (node (ref "C115") (pin "1") (pinfunction "1_1") (pintype "passive"))
      (node (ref "C116") (pin "1") (pinfunction "1_1") (pintype "passive"))
      (node (ref "J15") (pin "1") (pinfunction "VBUS_1") (pintype "passive"))
      (node (ref "R102") (pin "2") (pinfunction "2_2") (pintype "passive"))
      (node (ref "U6") (pin "5") (pinfunction "OUTB_5") (pintype "output"))
    )
    (net (code "74") (name "/VBUS_USB4") (class "Default")
      (node (ref "C113") (pin "1") (pinfunction "1_1") (pintype "passive"))
      (node (ref "C114") (pin "1") (pinfunction "1_1") (pintype "passive"))
      (node (ref "J15") (pin "10") (pinfunction "VBUS_10") (pintype "passive"))
      (node (ref "R103") (pin "2") (pinfunction "2_2") (pintype "passive"))
      (node (ref "U6") (pin "8") (pinfunction "OUTA_8") (pintype "output"))
    )
    (net (code "78") (name "1V05") (class "Default")
      (node (ref "C58") (pin "2") (pinfunction "2_2") (pintype "passive"))
      (node (ref "C59") (pin "2") (pinfunction "2_2") (pintype "passive"))
      (node (ref "C60") (pin "2") (pinfunction "2_2") (pintype "passive"))
      (node (ref "C61") (pin "2") (pinfunction "2_2") (pintype "passive"))
      (node (ref "C62") (pin "2") (pinfunction "2_2") (pintype "passive"))
      (node (ref "C63") (pin "2") (pinfunction "2_2") (pintype "passive"))
      (node (ref "C64") (pin "2") (pinfunction "2_2") (pintype "passive"))
      (node (ref "U13") (pin "12") (pinfunction "VDD10_12") (pintype "power_in"))
      (node (ref "U13") (pin "28") (pinfunction "VDD10_28") (pintype "power_in"))
      (node (ref "U13") (pin "37") (pinfunction "VDD10_37") (pintype "power_in"))
      (node (ref "U13") (pin "43") (pinfunction "VDD10_43") (pintype "power_in"))
      (node (ref "U13") (pin "46") (pinfunction "VDD10_46") (pintype "power_in"))
      (node (ref "U13") (pin "54") (pinfunction "VDD10_54") (pintype "power_in"))
      (node (ref "U13") (pin "60") (pinfunction "VDD10_60") (pintype "power_in"))
      (node (ref "U13") (pin "63") (pinfunction "VDD10_63") (pintype "power_in"))
      (node (ref "U13") (pin "9") (pinfunction "VDD10_9") (pintype "power_in"))
    )
    (net (code "79") (name "3V3") (class "Default")
      (node (ref "C110") (pin "2") (pinfunction "2_2") (pintype "passive"))
      (node (ref "C20") (pin "2") (pinfunction "2_2") (pintype "passive"))
      (node (ref "C23") (pin "2") (pinfunction "2_2") (pintype "passive"))
      (node (ref "C27") (pin "2") (pinfunction "2_2") (pintype "passive"))
      (node (ref "C55") (pin "2") (pinfunction "2_2") (pintype "passive"))
      (node (ref "C56") (pin "2") (pinfunction "2_2") (pintype "passive"))
      (node (ref "C57") (pin "2") (pinfunction "2_2") (pintype "passive"))
      (node (ref "C9") (pin "2") (pinfunction "2_2") (pintype "passive"))
      (node (ref "D3") (pin "1") (pinfunction "K_1") (pintype "passive"))
      (node (ref "IC1") (pin "8") (pinfunction "VCC_8") (pintype "power_in"))
      (node (ref "R112") (pin "2") (pinfunction "2_2") (pintype "passive"))
      (node (ref "R19") (pin "2") (pinfunction "2_2") (pintype "passive"))
      (node (ref "R20") (pin "2") (pinfunction "2_2") (pintype "passive"))
      (node (ref "R24") (pin "2") (pinfunction "2_2") (pintype "passive"))
      (node (ref "R38") (pin "2") (pinfunction "2_2") (pintype "passive"))
      (node (ref "R41") (pin "1") (pinfunction "1_1") (pintype "passive"))
      (node (ref "R46") (pin "1") (pinfunction "1_1") (pintype "passive"))
      (node (ref "R48") (pin "2") (pinfunction "2_2") (pintype "passive"))
      (node (ref "R49") (pin "2") (pinfunction "2_2") (pintype "passive"))
      (node (ref "R6") (pin "2") (pinfunction "2_2") (pintype "passive"))
      (node (ref "R87") (pin "2") (pinfunction "2_2") (pintype "passive"))
      (node (ref "R97") (pin "2") (pinfunction "2_2") (pintype "passive"))
      (node (ref "U13") (pin "15") (pinfunction "VDD33_15") (pintype "power_in"))
      (node (ref "U13") (pin "29") (pinfunction "VDD33_29") (pintype "power_in"))
      (node (ref "U13") (pin "32") (pinfunction "AVDD33_32") (pintype "power_in"))
      (node (ref "U13") (pin "40") (pinfunction "VDD33_40") (pintype "power_in"))
      (node (ref "U13") (pin "49") (pinfunction "VDD33_49") (pintype "power_in"))
      (node (ref "U13") (pin "57") (pinfunction "VDD33_57") (pintype "power_in"))
      (node (ref "U13") (pin "6") (pinfunction "AVDD33_6") (pintype "power_in"))
      (node (ref "U13") (pin "66") (pinfunction "VDD33_66") (pintype "power_in"))
    )
    (net (code "80") (name "GND") (class "Default")
      (node (ref "C110") (pin "1") (pinfunction "1_1") (pintype "passive"))
      (node (ref "C113") (pin "2") (pinfunction "2_2") (pintype "passive"))
      (node (ref "C114") (pin "2") (pinfunction "2_2") (pintype "passive"))
      (node (ref "C115") (pin "2") (pinfunction "2_2") (pintype "passive"))
      (node (ref "C116") (pin "2") (pinfunction "2_2") (pintype "passive"))
      (node (ref "C20") (pin "1") (pinfunction "1_1") (pintype "passive"))
      (node (ref "C23") (pin "1") (pinfunction "1_1") (pintype "passive"))
      (node (ref "C27") (pin "1") (pinfunction "1_1") (pintype "passive"))
      (node (ref "C55") (pin "1") (pinfunction "1_1") (pintype "passive"))
      (node (ref "C56") (pin "1") (pinfunction "1_1") (pintype "passive"))
      (node (ref "C57") (pin "1") (pinfunction "1_1") (pintype "passive"))
      (node (ref "C58") (pin "1") (pinfunction "1_1") (pintype "passive"))
      (node (ref "C59") (pin "1") (pinfunction "1_1") (pintype "passive"))
      (node (ref "C60") (pin "1") (pinfunction "1_1") (pintype "passive"))
      (node (ref "C61") (pin "1") (pinfunction "1_1") (pintype "passive"))
      (node (ref "C62") (pin "1") (pinfunction "1_1") (pintype "passive"))
      (node (ref "C63") (pin "1") (pinfunction "1_1") (pintype "passive"))
      (node (ref "C64") (pin "1") (pinfunction "1_1") (pintype "passive"))
      (node (ref "C65") (pin "1") (pinfunction "1_1") (pintype "passive"))
      (node (ref "C66") (pin "1") (pinfunction "1_1") (pintype "passive"))
      (node (ref "C67") (pin "1") (pinfunction "1_1") (pintype "passive"))
      (node (ref "C68") (pin "1") (pinfunction "1_1") (pintype "passive"))
      (node (ref "C9") (pin "1") (pinfunction "1_1") (pintype "passive"))
      (node (ref "C90") (pin "1") (pinfunction "1_1") (pintype "passive"))
      (node (ref "D10") (pin "1") (pinfunction "C_1") (pintype "passive"))
      (node (ref "D9") (pin "1") (pinfunction "C_1") (pintype "passive"))
      (node (ref "IC1") (pin "4") (pinfunction "GND_4") (pintype "power_in"))
      (node (ref "IC1") (pin "9") (pinfunction "EP_9") (pintype "passive"))
      (node (ref "J12") (pin "10") (pinfunction "SHLD5_10") (pintype "passive"))
      (node (ref "J12") (pin "11") (pinfunction "SHLD6_11") (pintype "passive"))
      (node (ref "J12") (pin "5") (pinfunction "GND_5") (pintype "passive"))
      (node (ref "J12") (pin "6") (pinfunction "SHLD1_6") (pintype "passive"))
      (node (ref "J12") (pin "7") (pinfunction "SHLD2_7") (pintype "passive"))
      (node (ref "J12") (pin "8") (pinfunction "SHLD3_8") (pintype "passive"))
      (node (ref "J12") (pin "9") (pinfunction "SHLD4_9") (pintype "passive"))
      (node (ref "J14") (pin "6") (pinfunction "6_6") (pintype "passive"))
      (node (ref "J14") (pin "9") (pinfunction "9_9") (pintype "passive"))
      (node (ref "J15") (pin "13") (pinfunction "GND_13") (pintype "passive"))
      (node (ref "J15") (pin "16") (pinfunction "GND_DRAIN_16") (pintype "passive"))
      (node (ref "J15") (pin "4") (pinfunction "GND_4") (pintype "passive"))
      (node (ref "J15") (pin "7") (pinfunction "GND_DRAIN_7") (pintype "passive"))
      (node (ref "R104") (pin "1") (pinfunction "1_1") (pintype "passive"))
      (node (ref "R105") (pin "1") (pinfunction "1_1") (pintype "passive"))
      (node (ref "R110") (pin "1") (pinfunction "1_1") (pintype "passive"))
      (node (ref "R111") (pin "1") (pinfunction "1_1") (pintype "passive"))
      (node (ref "R25") (pin "2") (pinfunction "2_2") (pintype "passive"))
      (node (ref "R39") (pin "2") (pinfunction "2_2") (pintype "passive"))
      (node (ref "U13") (pin "34") (pinfunction "IC(L)_34") (pintype "input"))
      (node (ref "U13") (pin "69") (pinfunction "GND_69") (pintype "power_in"))
      (node (ref "U6") (pin "6") (pinfunction "GND_6") (pintype "power_in"))
      (node (ref "Y2") (pin "2") (pinfunction "NC_2") (pintype "power_in"))
      (node (ref "Y2") (pin "4") (pinfunction "NC_4") (pintype "power_in"))
    )
    (net (code "81") (name "Net-(J14-Pad1)") (class "Default")
      (node (ref "J14") (pin "1") (pinfunction "1_1") (pintype "passive"))
      (node (ref "J14") (pin "3") (pinfunction "3_3") (pintype "passive"))
      (node (ref "R42") (pin "1") (pinfunction "1_1") (pintype "passive"))
    )
    (net (code "82") (name "Net-(U6-ENA)") (class "Default")
      (node (ref "R104") (pin "2") (pinfunction "2_2") (pintype "passive"))
      (node (ref "R98") (pin "1") (pinfunction "1_1") (pintype "passive"))
      (node (ref "U6") (pin "1") (pinfunction "ENA_1") (pintype "input"))
    )
    (net (code "83") (name "Net-(U6-ENB)") (class "Default")
      (node (ref "R105") (pin "2") (pinfunction "2_2") (pintype "passive"))
      (node (ref "R99") (pin "1") (pinfunction "1_1") (pintype "passive"))
      (node (ref "U6") (pin "4") (pinfunction "ENB_4") (pintype "input"))
    )
    (net (code "84") (name "Net-(U6-~{FLG}A)") (class "Default")
      (node (ref "R106") (pin "1") (pinfunction "1_1") (pintype "passive"))
      (node (ref "U6") (pin "2") (pinfunction "~{FLG}A_2") (pintype "open_collector"))
    )
    (net (code "85") (name "Net-(U6-~{FLG}B)") (class "Default")
      (node (ref "R107") (pin "1") (pinfunction "1_1") (pintype "passive"))
      (node (ref "U6") (pin "3") (pinfunction "~{FLG}B_3") (pintype "open_collector"))
    )
    (net (code "86") (name "USB_GND") (class "Default")
      (node (ref "C90") (pin "2") (pinfunction "2_2") (pintype "passive"))
      (node (ref "J15") (pin "Shell") (pinfunction "Shield_Shell") (pintype "passive"))
      (node (ref "R110") (pin "2") (pinfunction "2_2") (pintype "passive"))
    )
    (net (code "87") (name "VBUSB") (class "Default")
      (node (ref "J12") (pin "1") (pinfunction "VBUS_1") (pintype "passive"))
    )
    (net (code "88") (name "VDD_5V") (class "Default")
      (node (ref "R42") (pin "2") (pinfunction "2_2") (pintype "passive"))
      (node (ref "U6") (pin "7") (pinfunction "IN_7") (pintype "power_in"))
    )
    (net (code "89") (name "unconnected-(J12-ID-Pad4)") (class "Default")
      (node (ref "J12") (pin "4") (pinfunction "ID_4") (pintype "passive+no_connect"))
    )
    (net (code "90") (name "unconnected-(U13-PPON1-Pad27)") (class "Default")
      (node (ref "U13") (pin "27") (pinfunction "PPON1_27") (pintype "output+no_connect"))
    )
    (net (code "91") (name "unconnected-(U13-PPON2-Pad25)") (class "Default")
      (node (ref "U13") (pin "25") (pinfunction "PPON2_25") (pintype "output+no_connect"))
    )
  )
)
